# HDMI8x8_HSSwitchSet.net
KiCad netlist of a schematic drawn in Altium Designer
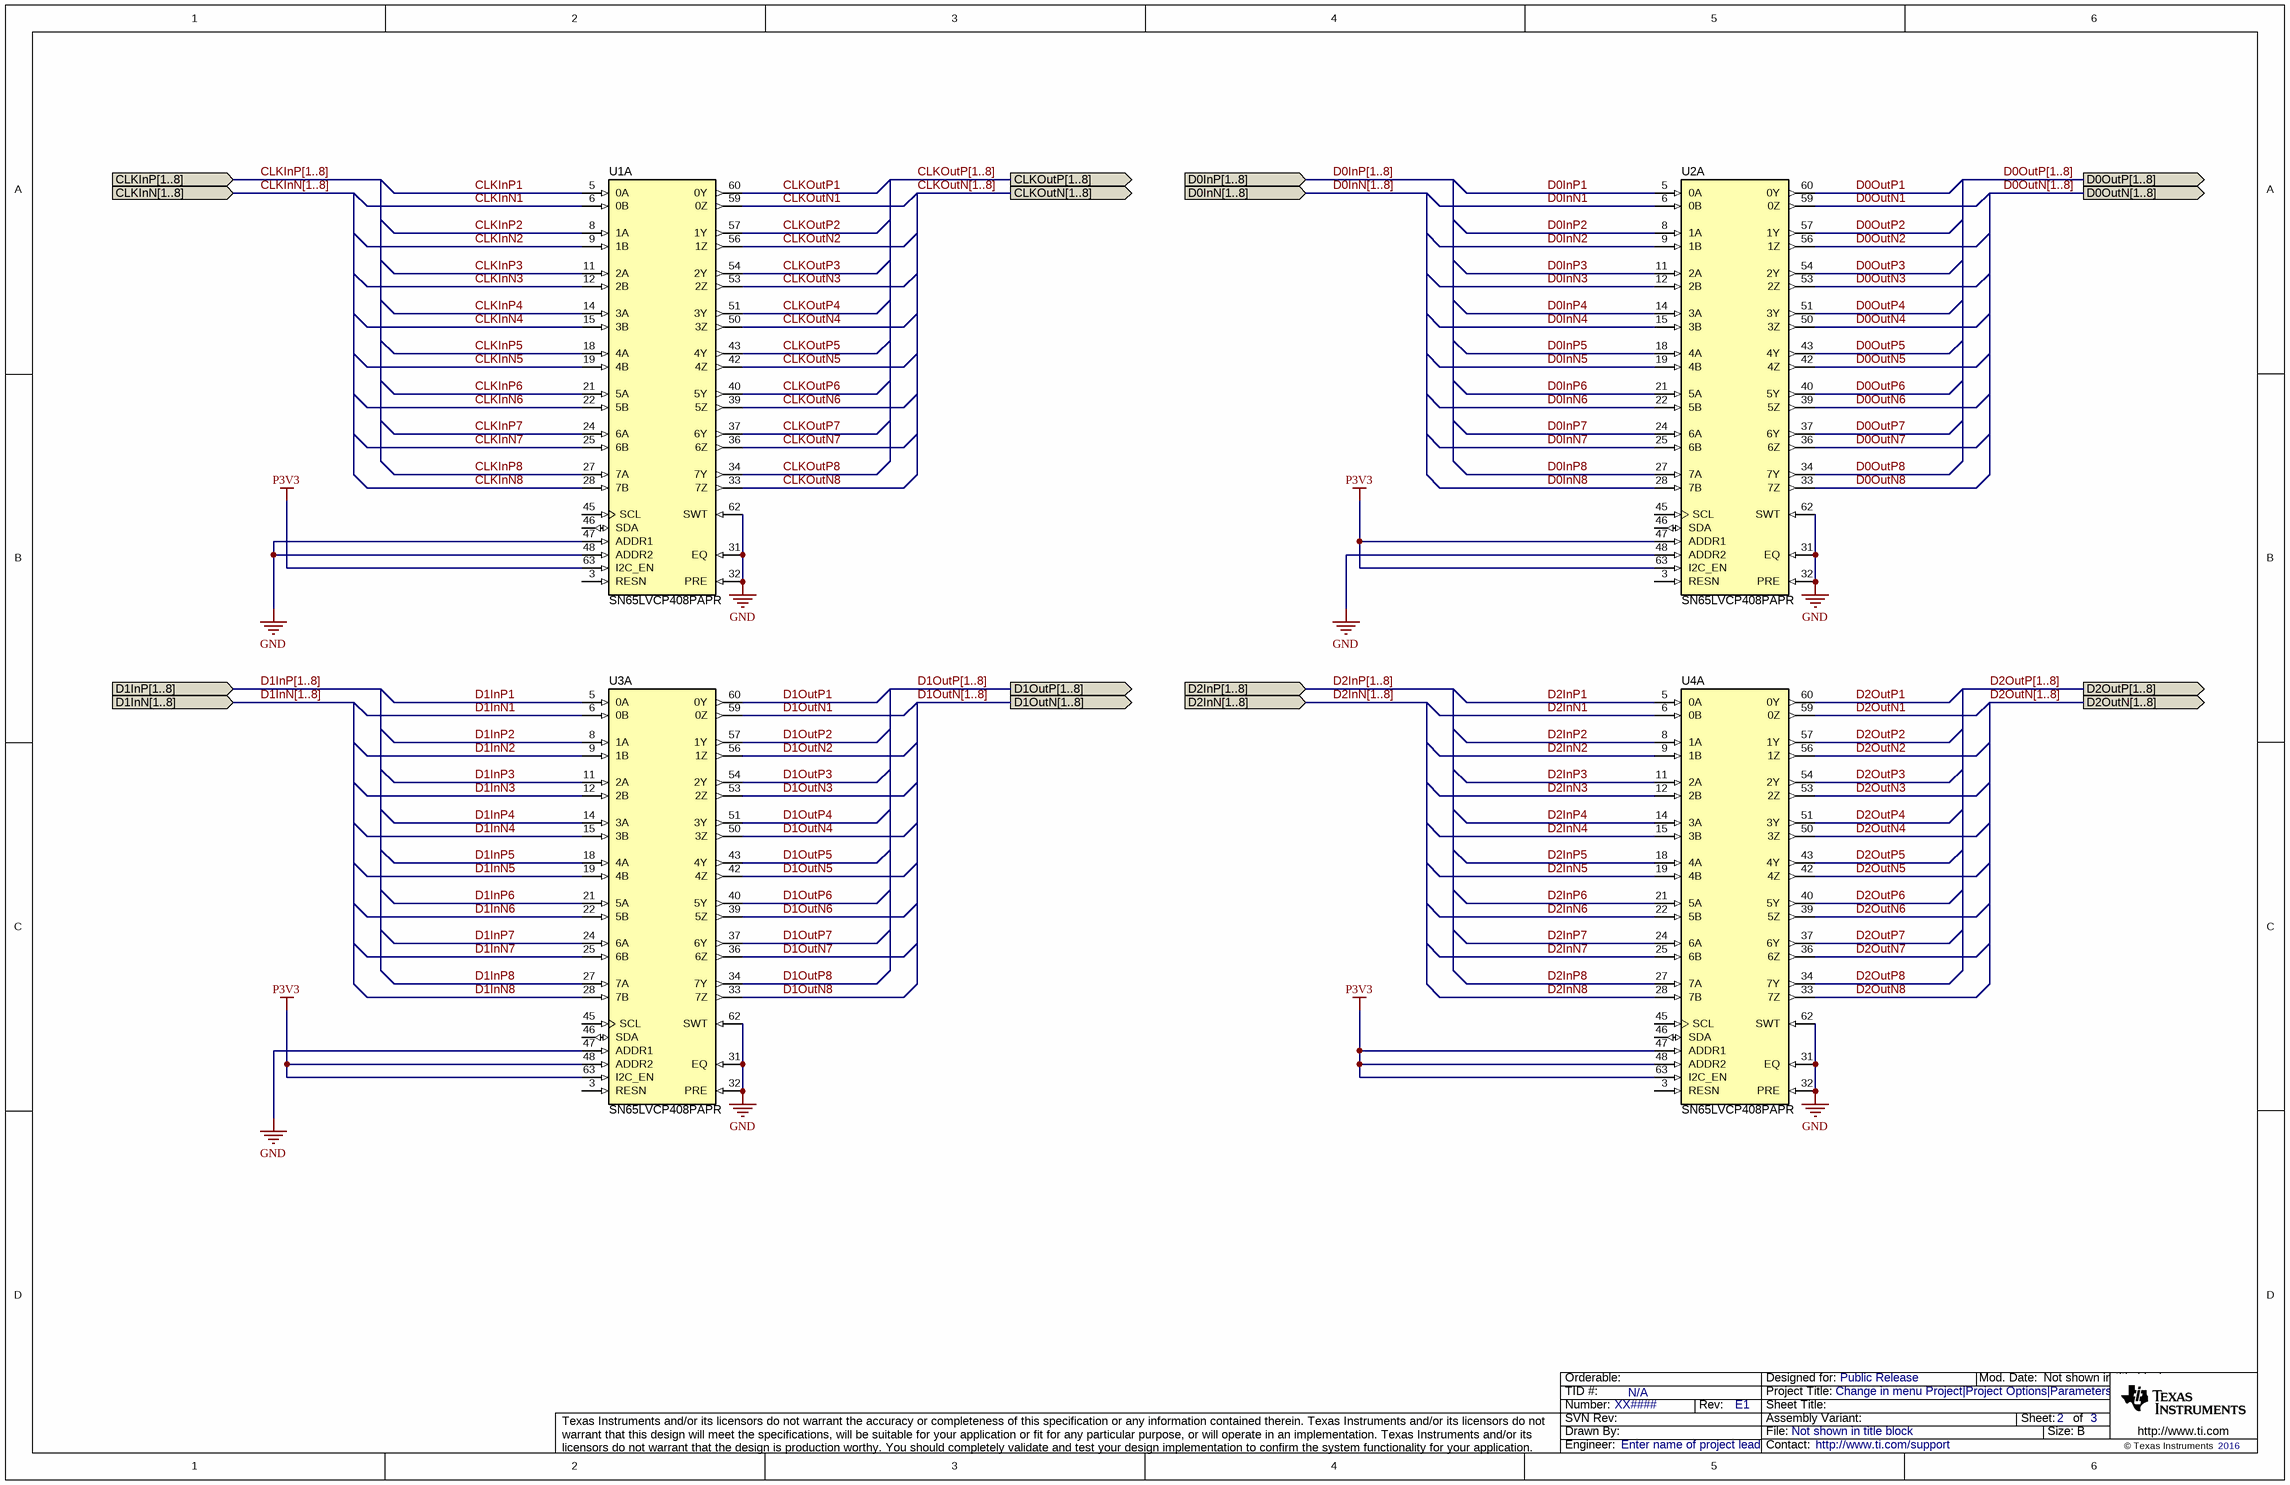
[diagram p0: HDMI8x8_HSSwitchSet.SchDoc]

(export (version "E")
  (design (tool "Eeschema 10.0.6"))
  (components
    (comp (ref "U1")
      (value "SN65LVCP408PAPR")
      (footprint "PAP0064D_N")
      (fields
        (field (name "MANUFACTURER") "Texas Instruments")
        (field (name "ALTERNATE PARTNUMBER") "Equivalent")
      )
      (libsource (lib "TI Interface Equalizer and Redriver") (part "SN65LVCP408PAPR"))
    )
    (comp (ref "U2")
      (value "SN65LVCP408PAPR")
      (footprint "PAP0064D_N")
      (fields
        (field (name "MANUFACTURER") "Texas Instruments")
        (field (name "ALTERNATE PARTNUMBER") "Equivalent")
      )
      (libsource (lib "TI Interface Equalizer and Redriver") (part "SN65LVCP408PAPR"))
    )
    (comp (ref "U3")
      (value "SN65LVCP408PAPR")
      (footprint "PAP0064D_N")
      (fields
        (field (name "MANUFACTURER") "Texas Instruments")
        (field (name "ALTERNATE PARTNUMBER") "Equivalent")
      )
      (libsource (lib "TI Interface Equalizer and Redriver") (part "SN65LVCP408PAPR"))
    )
    (comp (ref "U4")
      (value "SN65LVCP408PAPR")
      (footprint "PAP0064D_N")
      (fields
        (field (name "MANUFACTURER") "Texas Instruments")
        (field (name "ALTERNATE PARTNUMBER") "Equivalent")
      )
      (libsource (lib "TI Interface Equalizer and Redriver") (part "SN65LVCP408PAPR"))
    )
  )
  (nets
    (net (code "1") (name "/CLKInN1") (class "Default")
      (node (ref "U1") (pin "6") (pinfunction "0B_6") (pintype "input"))
    )
    (net (code "2") (name "/CLKInN2") (class "Default")
      (node (ref "U1") (pin "9") (pinfunction "1B_9") (pintype "input"))
    )
    (net (code "3") (name "/CLKInN3") (class "Default")
      (node (ref "U1") (pin "12") (pinfunction "2B_12") (pintype "input"))
    )
    (net (code "4") (name "/CLKInN4") (class "Default")
      (node (ref "U1") (pin "15") (pinfunction "3B_15") (pintype "input"))
    )
    (net (code "5") (name "/CLKInN5") (class "Default")
      (node (ref "U1") (pin "19") (pinfunction "4B_19") (pintype "input"))
    )
    (net (code "6") (name "/CLKInN6") (class "Default")
      (node (ref "U1") (pin "22") (pinfunction "5B_22") (pintype "input"))
    )
    (net (code "7") (name "/CLKInN7") (class "Default")
      (node (ref "U1") (pin "25") (pinfunction "6B_25") (pintype "input"))
    )
    (net (code "8") (name "/CLKInN8") (class "Default")
      (node (ref "U1") (pin "28") (pinfunction "7B_28") (pintype "input"))
    )
    (net (code "10") (name "/CLKInP1") (class "Default")
      (node (ref "U1") (pin "5") (pinfunction "0A_5") (pintype "input"))
    )
    (net (code "11") (name "/CLKInP2") (class "Default")
      (node (ref "U1") (pin "8") (pinfunction "1A_8") (pintype "input"))
    )
    (net (code "12") (name "/CLKInP3") (class "Default")
      (node (ref "U1") (pin "11") (pinfunction "2A_11") (pintype "input"))
    )
    (net (code "13") (name "/CLKInP4") (class "Default")
      (node (ref "U1") (pin "14") (pinfunction "3A_14") (pintype "input"))
    )
    (net (code "14") (name "/CLKInP5") (class "Default")
      (node (ref "U1") (pin "18") (pinfunction "4A_18") (pintype "input"))
    )
    (net (code "15") (name "/CLKInP6") (class "Default")
      (node (ref "U1") (pin "21") (pinfunction "5A_21") (pintype "input"))
    )
    (net (code "16") (name "/CLKInP7") (class "Default")
      (node (ref "U1") (pin "24") (pinfunction "6A_24") (pintype "input"))
    )
    (net (code "17") (name "/CLKInP8") (class "Default")
      (node (ref "U1") (pin "27") (pinfunction "7A_27") (pintype "input"))
    )
    (net (code "19") (name "/CLKOutN1") (class "Default")
      (node (ref "U1") (pin "59") (pinfunction "0Z_59") (pintype "output"))
    )
    (net (code "20") (name "/CLKOutN2") (class "Default")
      (node (ref "U1") (pin "56") (pinfunction "1Z_56") (pintype "output"))
    )
    (net (code "21") (name "/CLKOutN3") (class "Default")
      (node (ref "U1") (pin "53") (pinfunction "2Z_53") (pintype "output"))
    )
    (net (code "22") (name "/CLKOutN4") (class "Default")
      (node (ref "U1") (pin "50") (pinfunction "3Z_50") (pintype "output"))
    )
    (net (code "23") (name "/CLKOutN5") (class "Default")
      (node (ref "U1") (pin "42") (pinfunction "4Z_42") (pintype "output"))
    )
    (net (code "24") (name "/CLKOutN6") (class "Default")
      (node (ref "U1") (pin "39") (pinfunction "5Z_39") (pintype "output"))
    )
    (net (code "25") (name "/CLKOutN7") (class "Default")
      (node (ref "U1") (pin "36") (pinfunction "6Z_36") (pintype "output"))
    )
    (net (code "26") (name "/CLKOutN8") (class "Default")
      (node (ref "U1") (pin "33") (pinfunction "7Z_33") (pintype "output"))
    )
    (net (code "28") (name "/CLKOutP1") (class "Default")
      (node (ref "U1") (pin "60") (pinfunction "0Y_60") (pintype "output"))
    )
    (net (code "29") (name "/CLKOutP2") (class "Default")
      (node (ref "U1") (pin "57") (pinfunction "1Y_57") (pintype "output"))
    )
    (net (code "30") (name "/CLKOutP3") (class "Default")
      (node (ref "U1") (pin "54") (pinfunction "2Y_54") (pintype "output"))
    )
    (net (code "31") (name "/CLKOutP4") (class "Default")
      (node (ref "U1") (pin "51") (pinfunction "3Y_51") (pintype "output"))
    )
    (net (code "32") (name "/CLKOutP5") (class "Default")
      (node (ref "U1") (pin "43") (pinfunction "4Y_43") (pintype "output"))
    )
    (net (code "33") (name "/CLKOutP6") (class "Default")
      (node (ref "U1") (pin "40") (pinfunction "5Y_40") (pintype "output"))
    )
    (net (code "34") (name "/CLKOutP7") (class "Default")
      (node (ref "U1") (pin "37") (pinfunction "6Y_37") (pintype "output"))
    )
    (net (code "35") (name "/CLKOutP8") (class "Default")
      (node (ref "U1") (pin "34") (pinfunction "7Y_34") (pintype "output"))
    )
    (net (code "37") (name "/D0InN1") (class "Default")
      (node (ref "U2") (pin "6") (pinfunction "0B_6") (pintype "input"))
    )
    (net (code "38") (name "/D0InN2") (class "Default")
      (node (ref "U2") (pin "9") (pinfunction "1B_9") (pintype "input"))
    )
    (net (code "39") (name "/D0InN3") (class "Default")
      (node (ref "U2") (pin "12") (pinfunction "2B_12") (pintype "input"))
    )
    (net (code "40") (name "/D0InN4") (class "Default")
      (node (ref "U2") (pin "15") (pinfunction "3B_15") (pintype "input"))
    )
    (net (code "41") (name "/D0InN5") (class "Default")
      (node (ref "U2") (pin "19") (pinfunction "4B_19") (pintype "input"))
    )
    (net (code "42") (name "/D0InN6") (class "Default")
      (node (ref "U2") (pin "22") (pinfunction "5B_22") (pintype "input"))
    )
    (net (code "43") (name "/D0InN7") (class "Default")
      (node (ref "U2") (pin "25") (pinfunction "6B_25") (pintype "input"))
    )
    (net (code "44") (name "/D0InN8") (class "Default")
      (node (ref "U2") (pin "28") (pinfunction "7B_28") (pintype "input"))
    )
    (net (code "46") (name "/D0InP1") (class "Default")
      (node (ref "U2") (pin "5") (pinfunction "0A_5") (pintype "input"))
    )
    (net (code "47") (name "/D0InP2") (class "Default")
      (node (ref "U2") (pin "8") (pinfunction "1A_8") (pintype "input"))
    )
    (net (code "48") (name "/D0InP3") (class "Default")
      (node (ref "U2") (pin "11") (pinfunction "2A_11") (pintype "input"))
    )
    (net (code "49") (name "/D0InP4") (class "Default")
      (node (ref "U2") (pin "14") (pinfunction "3A_14") (pintype "input"))
    )
    (net (code "50") (name "/D0InP5") (class "Default")
      (node (ref "U2") (pin "18") (pinfunction "4A_18") (pintype "input"))
    )
    (net (code "51") (name "/D0InP6") (class "Default")
      (node (ref "U2") (pin "21") (pinfunction "5A_21") (pintype "input"))
    )
    (net (code "52") (name "/D0InP7") (class "Default")
      (node (ref "U2") (pin "24") (pinfunction "6A_24") (pintype "input"))
    )
    (net (code "53") (name "/D0InP8") (class "Default")
      (node (ref "U2") (pin "27") (pinfunction "7A_27") (pintype "input"))
    )
    (net (code "55") (name "/D0OutN1") (class "Default")
      (node (ref "U2") (pin "59") (pinfunction "0Z_59") (pintype "output"))
    )
    (net (code "56") (name "/D0OutN2") (class "Default")
      (node (ref "U2") (pin "56") (pinfunction "1Z_56") (pintype "output"))
    )
    (net (code "57") (name "/D0OutN3") (class "Default")
      (node (ref "U2") (pin "53") (pinfunction "2Z_53") (pintype "output"))
    )
    (net (code "58") (name "/D0OutN4") (class "Default")
      (node (ref "U2") (pin "50") (pinfunction "3Z_50") (pintype "output"))
    )
    (net (code "59") (name "/D0OutN5") (class "Default")
      (node (ref "U2") (pin "42") (pinfunction "4Z_42") (pintype "output"))
    )
    (net (code "60") (name "/D0OutN6") (class "Default")
      (node (ref "U2") (pin "39") (pinfunction "5Z_39") (pintype "output"))
    )
    (net (code "61") (name "/D0OutN7") (class "Default")
      (node (ref "U2") (pin "36") (pinfunction "6Z_36") (pintype "output"))
    )
    (net (code "62") (name "/D0OutN8") (class "Default")
      (node (ref "U2") (pin "33") (pinfunction "7Z_33") (pintype "output"))
    )
    (net (code "64") (name "/D0OutP1") (class "Default")
      (node (ref "U2") (pin "60") (pinfunction "0Y_60") (pintype "output"))
    )
    (net (code "65") (name "/D0OutP2") (class "Default")
      (node (ref "U2") (pin "57") (pinfunction "1Y_57") (pintype "output"))
    )
    (net (code "66") (name "/D0OutP3") (class "Default")
      (node (ref "U2") (pin "54") (pinfunction "2Y_54") (pintype "output"))
    )
    (net (code "67") (name "/D0OutP4") (class "Default")
      (node (ref "U2") (pin "51") (pinfunction "3Y_51") (pintype "output"))
    )
    (net (code "68") (name "/D0OutP5") (class "Default")
      (node (ref "U2") (pin "43") (pinfunction "4Y_43") (pintype "output"))
    )
    (net (code "69") (name "/D0OutP6") (class "Default")
      (node (ref "U2") (pin "40") (pinfunction "5Y_40") (pintype "output"))
    )
    (net (code "70") (name "/D0OutP7") (class "Default")
      (node (ref "U2") (pin "37") (pinfunction "6Y_37") (pintype "output"))
    )
    (net (code "71") (name "/D0OutP8") (class "Default")
      (node (ref "U2") (pin "34") (pinfunction "7Y_34") (pintype "output"))
    )
    (net (code "73") (name "/D1InN1") (class "Default")
      (node (ref "U3") (pin "6") (pinfunction "0B_6") (pintype "input"))
    )
    (net (code "74") (name "/D1InN2") (class "Default")
      (node (ref "U3") (pin "9") (pinfunction "1B_9") (pintype "input"))
    )
    (net (code "75") (name "/D1InN3") (class "Default")
      (node (ref "U3") (pin "12") (pinfunction "2B_12") (pintype "input"))
    )
    (net (code "76") (name "/D1InN4") (class "Default")
      (node (ref "U3") (pin "15") (pinfunction "3B_15") (pintype "input"))
    )
    (net (code "77") (name "/D1InN5") (class "Default")
      (node (ref "U3") (pin "19") (pinfunction "4B_19") (pintype "input"))
    )
    (net (code "78") (name "/D1InN6") (class "Default")
      (node (ref "U3") (pin "22") (pinfunction "5B_22") (pintype "input"))
    )
    (net (code "79") (name "/D1InN7") (class "Default")
      (node (ref "U3") (pin "25") (pinfunction "6B_25") (pintype "input"))
    )
    (net (code "80") (name "/D1InN8") (class "Default")
      (node (ref "U3") (pin "28") (pinfunction "7B_28") (pintype "input"))
    )
    (net (code "82") (name "/D1InP1") (class "Default")
      (node (ref "U3") (pin "5") (pinfunction "0A_5") (pintype "input"))
    )
    (net (code "83") (name "/D1InP2") (class "Default")
      (node (ref "U3") (pin "8") (pinfunction "1A_8") (pintype "input"))
    )
    (net (code "84") (name "/D1InP3") (class "Default")
      (node (ref "U3") (pin "11") (pinfunction "2A_11") (pintype "input"))
    )
    (net (code "85") (name "/D1InP4") (class "Default")
      (node (ref "U3") (pin "14") (pinfunction "3A_14") (pintype "input"))
    )
    (net (code "86") (name "/D1InP5") (class "Default")
      (node (ref "U3") (pin "18") (pinfunction "4A_18") (pintype "input"))
    )
    (net (code "87") (name "/D1InP6") (class "Default")
      (node (ref "U3") (pin "21") (pinfunction "5A_21") (pintype "input"))
    )
    (net (code "88") (name "/D1InP7") (class "Default")
      (node (ref "U3") (pin "24") (pinfunction "6A_24") (pintype "input"))
    )
    (net (code "89") (name "/D1InP8") (class "Default")
      (node (ref "U3") (pin "27") (pinfunction "7A_27") (pintype "input"))
    )
    (net (code "91") (name "/D1OutN1") (class "Default")
      (node (ref "U3") (pin "59") (pinfunction "0Z_59") (pintype "output"))
    )
    (net (code "92") (name "/D1OutN2") (class "Default")
      (node (ref "U3") (pin "56") (pinfunction "1Z_56") (pintype "output"))
    )
    (net (code "93") (name "/D1OutN3") (class "Default")
      (node (ref "U3") (pin "53") (pinfunction "2Z_53") (pintype "output"))
    )
    (net (code "94") (name "/D1OutN4") (class "Default")
      (node (ref "U3") (pin "50") (pinfunction "3Z_50") (pintype "output"))
    )
    (net (code "95") (name "/D1OutN5") (class "Default")
      (node (ref "U3") (pin "42") (pinfunction "4Z_42") (pintype "output"))
    )
    (net (code "96") (name "/D1OutN6") (class "Default")
      (node (ref "U3") (pin "39") (pinfunction "5Z_39") (pintype "output"))
    )
    (net (code "97") (name "/D1OutN7") (class "Default")
      (node (ref "U3") (pin "36") (pinfunction "6Z_36") (pintype "output"))
    )
    (net (code "98") (name "/D1OutN8") (class "Default")
      (node (ref "U3") (pin "33") (pinfunction "7Z_33") (pintype "output"))
    )
    (net (code "100") (name "/D1OutP1") (class "Default")
      (node (ref "U3") (pin "60") (pinfunction "0Y_60") (pintype "output"))
    )
    (net (code "101") (name "/D1OutP2") (class "Default")
      (node (ref "U3") (pin "57") (pinfunction "1Y_57") (pintype "output"))
    )
    (net (code "102") (name "/D1OutP3") (class "Default")
      (node (ref "U3") (pin "54") (pinfunction "2Y_54") (pintype "output"))
    )
    (net (code "103") (name "/D1OutP4") (class "Default")
      (node (ref "U3") (pin "51") (pinfunction "3Y_51") (pintype "output"))
    )
    (net (code "104") (name "/D1OutP5") (class "Default")
      (node (ref "U3") (pin "43") (pinfunction "4Y_43") (pintype "output"))
    )
    (net (code "105") (name "/D1OutP6") (class "Default")
      (node (ref "U3") (pin "40") (pinfunction "5Y_40") (pintype "output"))
    )
    (net (code "106") (name "/D1OutP7") (class "Default")
      (node (ref "U3") (pin "37") (pinfunction "6Y_37") (pintype "output"))
    )
    (net (code "107") (name "/D1OutP8") (class "Default")
      (node (ref "U3") (pin "34") (pinfunction "7Y_34") (pintype "output"))
    )
    (net (code "109") (name "/D2InN1") (class "Default")
      (node (ref "U4") (pin "6") (pinfunction "0B_6") (pintype "input"))
    )
    (net (code "110") (name "/D2InN2") (class "Default")
      (node (ref "U4") (pin "9") (pinfunction "1B_9") (pintype "input"))
    )
    (net (code "111") (name "/D2InN3") (class "Default")
      (node (ref "U4") (pin "12") (pinfunction "2B_12") (pintype "input"))
    )
    (net (code "112") (name "/D2InN4") (class "Default")
      (node (ref "U4") (pin "15") (pinfunction "3B_15") (pintype "input"))
    )
    (net (code "113") (name "/D2InN5") (class "Default")
      (node (ref "U4") (pin "19") (pinfunction "4B_19") (pintype "input"))
    )
    (net (code "114") (name "/D2InN6") (class "Default")
      (node (ref "U4") (pin "22") (pinfunction "5B_22") (pintype "input"))
    )
    (net (code "115") (name "/D2InN7") (class "Default")
      (node (ref "U4") (pin "25") (pinfunction "6B_25") (pintype "input"))
    )
    (net (code "116") (name "/D2InN8") (class "Default")
      (node (ref "U4") (pin "28") (pinfunction "7B_28") (pintype "input"))
    )
    (net (code "118") (name "/D2InP1") (class "Default")
      (node (ref "U4") (pin "5") (pinfunction "0A_5") (pintype "input"))
    )
    (net (code "119") (name "/D2InP2") (class "Default")
      (node (ref "U4") (pin "8") (pinfunction "1A_8") (pintype "input"))
    )
    (net (code "120") (name "/D2InP3") (class "Default")
      (node (ref "U4") (pin "11") (pinfunction "2A_11") (pintype "input"))
    )
    (net (code "121") (name "/D2InP4") (class "Default")
      (node (ref "U4") (pin "14") (pinfunction "3A_14") (pintype "input"))
    )
    (net (code "122") (name "/D2InP5") (class "Default")
      (node (ref "U4") (pin "18") (pinfunction "4A_18") (pintype "input"))
    )
    (net (code "123") (name "/D2InP6") (class "Default")
      (node (ref "U4") (pin "21") (pinfunction "5A_21") (pintype "input"))
    )
    (net (code "124") (name "/D2InP7") (class "Default")
      (node (ref "U4") (pin "24") (pinfunction "6A_24") (pintype "input"))
    )
    (net (code "125") (name "/D2InP8") (class "Default")
      (node (ref "U4") (pin "27") (pinfunction "7A_27") (pintype "input"))
    )
    (net (code "127") (name "/D2OutN1") (class "Default")
      (node (ref "U4") (pin "59") (pinfunction "0Z_59") (pintype "output"))
    )
    (net (code "128") (name "/D2OutN2") (class "Default")
      (node (ref "U4") (pin "56") (pinfunction "1Z_56") (pintype "output"))
    )
    (net (code "129") (name "/D2OutN3") (class "Default")
      (node (ref "U4") (pin "53") (pinfunction "2Z_53") (pintype "output"))
    )
    (net (code "130") (name "/D2OutN4") (class "Default")
      (node (ref "U4") (pin "50") (pinfunction "3Z_50") (pintype "output"))
    )
    (net (code "131") (name "/D2OutN5") (class "Default")
      (node (ref "U4") (pin "42") (pinfunction "4Z_42") (pintype "output"))
    )
    (net (code "132") (name "/D2OutN6") (class "Default")
      (node (ref "U4") (pin "39") (pinfunction "5Z_39") (pintype "output"))
    )
    (net (code "133") (name "/D2OutN7") (class "Default")
      (node (ref "U4") (pin "36") (pinfunction "6Z_36") (pintype "output"))
    )
    (net (code "134") (name "/D2OutN8") (class "Default")
      (node (ref "U4") (pin "33") (pinfunction "7Z_33") (pintype "output"))
    )
    (net (code "136") (name "/D2OutP1") (class "Default")
      (node (ref "U4") (pin "60") (pinfunction "0Y_60") (pintype "output"))
    )
    (net (code "137") (name "/D2OutP2") (class "Default")
      (node (ref "U4") (pin "57") (pinfunction "1Y_57") (pintype "output"))
    )
    (net (code "138") (name "/D2OutP3") (class "Default")
      (node (ref "U4") (pin "54") (pinfunction "2Y_54") (pintype "output"))
    )
    (net (code "139") (name "/D2OutP4") (class "Default")
      (node (ref "U4") (pin "51") (pinfunction "3Y_51") (pintype "output"))
    )
    (net (code "140") (name "/D2OutP5") (class "Default")
      (node (ref "U4") (pin "43") (pinfunction "4Y_43") (pintype "output"))
    )
    (net (code "141") (name "/D2OutP6") (class "Default")
      (node (ref "U4") (pin "40") (pinfunction "5Y_40") (pintype "output"))
    )
    (net (code "142") (name "/D2OutP7") (class "Default")
      (node (ref "U4") (pin "37") (pinfunction "6Y_37") (pintype "output"))
    )
    (net (code "143") (name "/D2OutP8") (class "Default")
      (node (ref "U4") (pin "34") (pinfunction "7Y_34") (pintype "output"))
    )
    (net (code "145") (name "GND") (class "Default")
      (node (ref "U1") (pin "31") (pinfunction "EQ_31") (pintype "input"))
      (node (ref "U1") (pin "32") (pinfunction "PRE_32") (pintype "input"))
      (node (ref "U1") (pin "47") (pinfunction "ADDR1_47") (pintype "input"))
      (node (ref "U1") (pin "48") (pinfunction "ADDR2_48") (pintype "input"))
      (node (ref "U1") (pin "62") (pinfunction "SWT_62") (pintype "input"))
      (node (ref "U2") (pin "31") (pinfunction "EQ_31") (pintype "input"))
      (node (ref "U2") (pin "32") (pinfunction "PRE_32") (pintype "input"))
      (node (ref "U2") (pin "48") (pinfunction "ADDR2_48") (pintype "input"))
      (node (ref "U2") (pin "62") (pinfunction "SWT_62") (pintype "input"))
      (node (ref "U3") (pin "31") (pinfunction "EQ_31") (pintype "input"))
      (node (ref "U3") (pin "32") (pinfunction "PRE_32") (pintype "input"))
      (node (ref "U3") (pin "47") (pinfunction "ADDR1_47") (pintype "input"))
      (node (ref "U3") (pin "62") (pinfunction "SWT_62") (pintype "input"))
      (node (ref "U4") (pin "31") (pinfunction "EQ_31") (pintype "input"))
      (node (ref "U4") (pin "32") (pinfunction "PRE_32") (pintype "input"))
      (node (ref "U4") (pin "62") (pinfunction "SWT_62") (pintype "input"))
    )
    (net (code "146") (name "P3V3") (class "Default")
      (node (ref "U1") (pin "63") (pinfunction "I2C_EN_63") (pintype "input"))
      (node (ref "U2") (pin "47") (pinfunction "ADDR1_47") (pintype "input"))
      (node (ref "U2") (pin "63") (pinfunction "I2C_EN_63") (pintype "input"))
      (node (ref "U3") (pin "48") (pinfunction "ADDR2_48") (pintype "input"))
      (node (ref "U3") (pin "63") (pinfunction "I2C_EN_63") (pintype "input"))
      (node (ref "U4") (pin "47") (pinfunction "ADDR1_47") (pintype "input"))
      (node (ref "U4") (pin "48") (pinfunction "ADDR2_48") (pintype "input"))
      (node (ref "U4") (pin "63") (pinfunction "I2C_EN_63") (pintype "input"))
    )
    (net (code "147") (name "unconnected-(U1A-RESN-Pad3)") (class "Default")
      (node (ref "U1") (pin "3") (pinfunction "RESN_3") (pintype "input"))
    )
    (net (code "148") (name "unconnected-(U1A-SCL-Pad45)") (class "Default")
      (node (ref "U1") (pin "45") (pinfunction "SCL_45") (pintype "input"))
    )
    (net (code "149") (name "unconnected-(U1A-SDA-Pad46)") (class "Default")
      (node (ref "U1") (pin "46") (pinfunction "SDA_46") (pintype "bidirectional"))
    )
    (net (code "150") (name "unconnected-(U2A-RESN-Pad3)") (class "Default")
      (node (ref "U2") (pin "3") (pinfunction "RESN_3") (pintype "input"))
    )
    (net (code "151") (name "unconnected-(U2A-SCL-Pad45)") (class "Default")
      (node (ref "U2") (pin "45") (pinfunction "SCL_45") (pintype "input"))
    )
    (net (code "152") (name "unconnected-(U2A-SDA-Pad46)") (class "Default")
      (node (ref "U2") (pin "46") (pinfunction "SDA_46") (pintype "bidirectional"))
    )
    (net (code "153") (name "unconnected-(U3A-RESN-Pad3)") (class "Default")
      (node (ref "U3") (pin "3") (pinfunction "RESN_3") (pintype "input"))
    )
    (net (code "154") (name "unconnected-(U3A-SCL-Pad45)") (class "Default")
      (node (ref "U3") (pin "45") (pinfunction "SCL_45") (pintype "input"))
    )
    (net (code "155") (name "unconnected-(U3A-SDA-Pad46)") (class "Default")
      (node (ref "U3") (pin "46") (pinfunction "SDA_46") (pintype "bidirectional"))
    )
    (net (code "156") (name "unconnected-(U4A-RESN-Pad3)") (class "Default")
      (node (ref "U4") (pin "3") (pinfunction "RESN_3") (pintype "input"))
    )
    (net (code "157") (name "unconnected-(U4A-SCL-Pad45)") (class "Default")
      (node (ref "U4") (pin "45") (pinfunction "SCL_45") (pintype "input"))
    )
    (net (code "158") (name "unconnected-(U4A-SDA-Pad46)") (class "Default")
      (node (ref "U4") (pin "46") (pinfunction "SDA_46") (pintype "bidirectional"))
    )
  )
)
